# 2014-9-17.net
KiCad netlist of a schematic drawn in Altium Designer
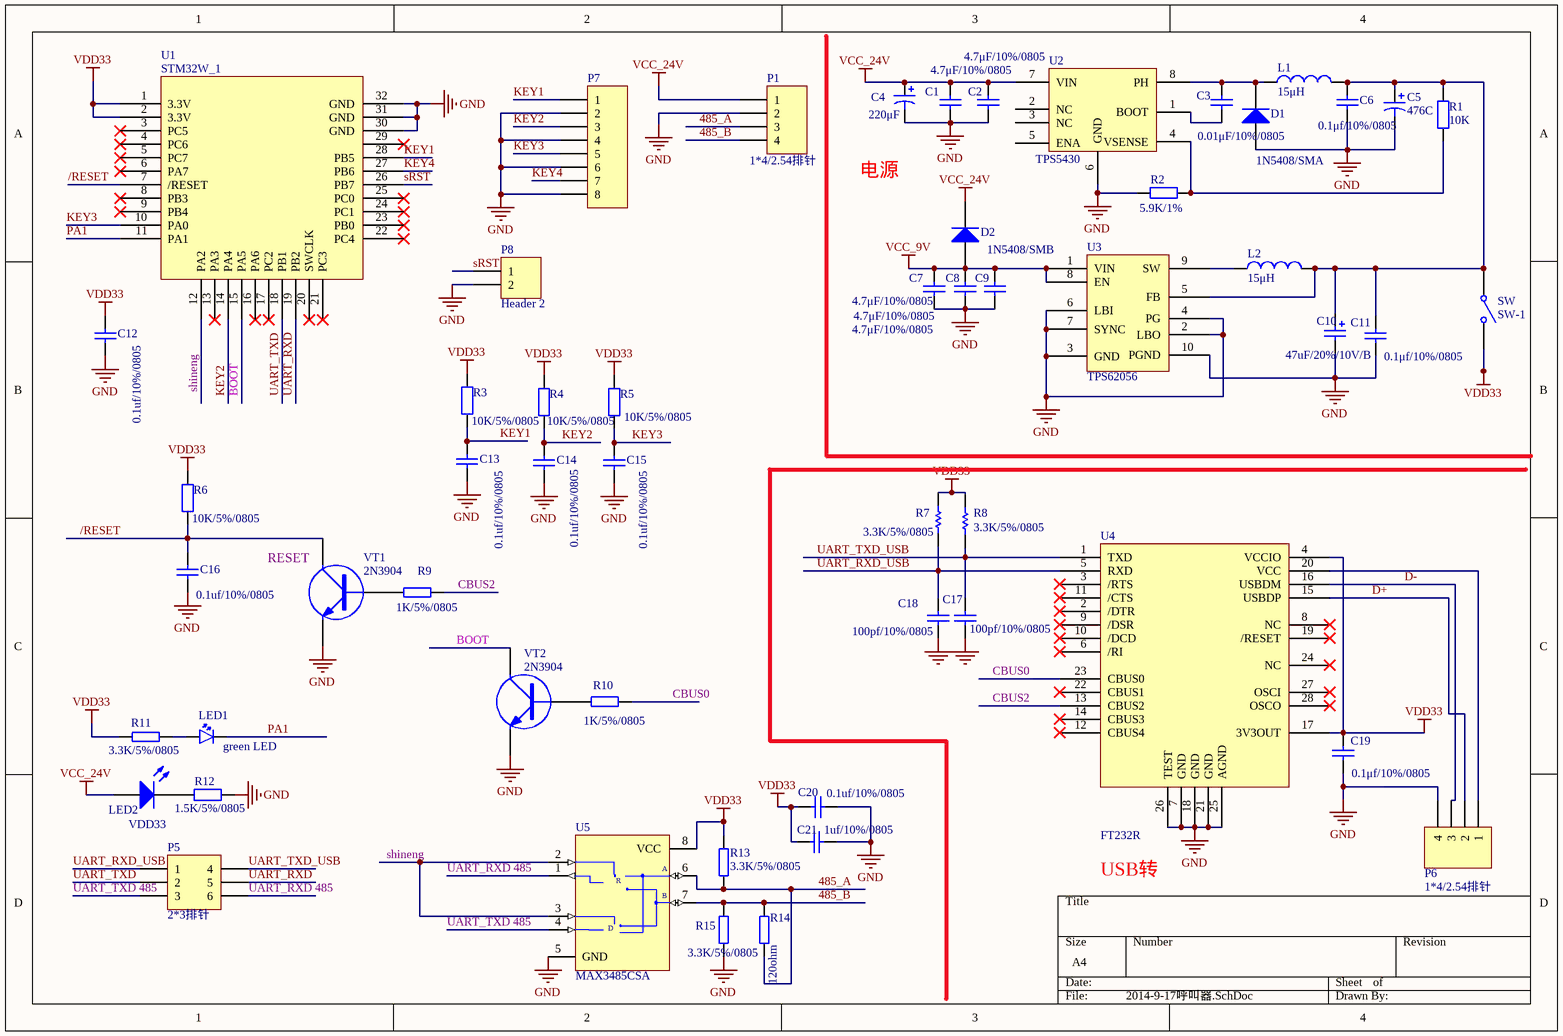
[diagram p0: 2014-9-17呼叫器.SchDoc]

(export (version "E")
  (design (tool "Eeschema 10.0.6"))
  (components
    (comp (ref "C1")
      (value "4.7μF/10%/0805")
      (footprint "C-0805")
      (description "Capacitor")
      (fields (field (name "PUBLISHER") "Altium Limited"))
      (libsource (lib "Miscellaneous Devices") (part "Cap"))
    )
    (comp (ref "C2")
      (value "4.7μF/10%/0805")
      (footprint "C-0805")
      (description "Capacitor")
      (fields (field (name "PUBLISHER") "Altium Limited"))
      (libsource (lib "Miscellaneous Devices") (part "Cap"))
    )
    (comp (ref "C3")
      (value "0.01μF/10%/0805")
      (footprint "C-0805")
      (description "Capacitor")
      (fields (field (name "PUBLISHER") "Altium Limited"))
      (libsource (lib "Miscellaneous Devices") (part "Cap"))
    )
    (comp (ref "C4")
      (value "220μF")
      (footprint "CZ3.0/6.5")
      (description "Polarized Capacitor (Radial)")
      (fields (field (name "PUBLISHER") "Altium Limited"))
      (libsource (lib "Miscellaneous Devices") (part "Cap Pol1"))
    )
    (comp (ref "C5")
      (value "476C")
      (footprint "C-TAN-D")
      (description "Polarized Capacitor (Radial)")
      (fields (field (name "PUBLISHER") "Altium Limited"))
      (libsource (lib "Miscellaneous Devices") (part "Cap Pol1"))
    )
    (comp (ref "C6")
      (value "0.1μf/10%/0805")
      (footprint "C-0805")
      (description "Capacitor")
      (fields (field (name "PUBLISHER") "Altium Limited"))
      (libsource (lib "Miscellaneous Devices") (part "Cap"))
    )
    (comp (ref "C7")
      (value "4.7μF/10%/0805")
      (footprint "C-0805")
      (description "Capacitor")
      (fields (field (name "PUBLISHER") "Altium Limited"))
      (libsource (lib "Miscellaneous Devices") (part "Cap"))
    )
    (comp (ref "C8")
      (value "4.7μF/10%/0805")
      (footprint "C-0805")
      (description "Capacitor")
      (fields (field (name "PUBLISHER") "Altium Limited"))
      (libsource (lib "Miscellaneous Devices") (part "Cap"))
    )
    (comp (ref "C9")
      (value "4.7μF/10%/0805")
      (footprint "C-0805")
      (description "Capacitor")
      (fields (field (name "PUBLISHER") "Altium Limited"))
      (libsource (lib "Miscellaneous Devices") (part "Cap"))
    )
    (comp (ref "C10")
      (value "47uF/20%/10V/B")
      (footprint "C-TAN-B")
      (libsource (lib "浙江关西电机数据库") (part "CAP_polarity"))
    )
    (comp (ref "C11")
      (value "0.1μf/10%/0805")
      (footprint "C-0805")
      (description "Capacitor")
      (fields (field (name "PUBLISHER") "Altium Limited"))
      (libsource (lib "Miscellaneous Devices") (part "Cap"))
    )
    (comp (ref "C12")
      (value "0.1uf/10%/0805")
      (footprint "C-0805")
      (description "Capacitor")
      (fields (field (name "PUBLISHER") "Altium Limited"))
      (libsource (lib "Miscellaneous Devices") (part "Cap"))
    )
    (comp (ref "C13")
      (value "0.1uf/10%/0805")
      (footprint "C-0805")
      (description "Capacitor")
      (fields (field (name "PUBLISHER") "Altium Limited"))
      (libsource (lib "Miscellaneous Devices") (part "Cap"))
    )
    (comp (ref "C14")
      (value "0.1uf/10%/0805")
      (footprint "C-0805")
      (description "Capacitor")
      (fields (field (name "PUBLISHER") "Altium Limited"))
      (libsource (lib "Miscellaneous Devices") (part "Cap"))
    )
    (comp (ref "C15")
      (value "0.1uf/10%/0805")
      (footprint "C-0805")
      (description "Capacitor")
      (fields (field (name "PUBLISHER") "Altium Limited"))
      (libsource (lib "Miscellaneous Devices") (part "Cap"))
    )
    (comp (ref "C16")
      (value "0.1uf/10%/0805")
      (footprint "C-0805")
      (description "Capacitor")
      (fields (field (name "PUBLISHER") "Altium Limited"))
      (libsource (lib "Miscellaneous Devices") (part "Cap"))
    )
    (comp (ref "C17")
      (value "100pf/10%/0805")
      (footprint "C-0805")
      (description "Capacitor")
      (fields (field (name "PUBLISHER") "Altium Limited"))
      (libsource (lib "Miscellaneous Devices") (part "Cap"))
    )
    (comp (ref "C18")
      (value "100pf/10%/0805")
      (footprint "C-0805")
      (description "Capacitor")
      (fields (field (name "PUBLISHER") "Altium Limited"))
      (libsource (lib "Miscellaneous Devices") (part "Cap"))
    )
    (comp (ref "C19")
      (value "0.1μf/10%/0805")
      (footprint "C-0805")
      (description "Capacitor")
      (fields (field (name "PUBLISHER") "Altium Limited"))
      (libsource (lib "Miscellaneous Devices") (part "Cap"))
    )
    (comp (ref "C20")
      (value "0.1uf/10%/0805")
      (footprint "C-0805")
      (description "Capacitor")
      (fields (field (name "PUBLISHER") "Altium Limited"))
      (libsource (lib "Miscellaneous Devices") (part "Cap"))
    )
    (comp (ref "C21")
      (value "1uf/10%/0805")
      (footprint "C-0805")
      (description "Capacitor")
      (fields (field (name "PUBLISHER") "Altium Limited"))
      (libsource (lib "Miscellaneous Devices") (part "Cap"))
    )
    (comp (ref "D1")
      (value "1N5408/SMA")
      (footprint "SMA 2+")
      (description "3 Amp Medium Power Silicon Rectifier Diode")
      (fields (field (name "PUBLISHER") "Altium Limited"))
      (libsource (lib "Miscellaneous Devices") (part "Diode 1N5408"))
    )
    (comp (ref "D2")
      (value "1N5408/SMB")
      (footprint "smb")
      (description "3 Amp Medium Power Silicon Rectifier Diode")
      (fields (field (name "PUBLISHER") "Altium Limited"))
      (libsource (lib "Miscellaneous Devices") (part "Diode 1N5408"))
    )
    (comp (ref "L1")
      (value "15μH")
      (footprint "GSDS104C2")
      (description "Inductor")
      (fields (field (name "PUBLISHER") "Altium Limited"))
      (libsource (lib "Miscellaneous Devices") (part "Inductor"))
    )
    (comp (ref "L2")
      (value "15μH")
      (footprint "GSDS104C2")
      (description "Inductor")
      (fields (field (name "PUBLISHER") "Altium Limited"))
      (libsource (lib "Miscellaneous Devices") (part "Inductor"))
    )
    (comp (ref "LED1") (value "green LED") (footprint "LED-φ3") (libsource (lib "Haze") (part "LED")))
    (comp (ref "LED2")
      (value "VDD33")
      (footprint "LED-φ3")
      (description "Typical BLUE SiC LED")
      (fields (field (name "PUBLISHER") "Altium Limited"))
      (libsource (lib "Miscellaneous Devices") (part "LED3"))
    )
    (comp (ref "P1")
      (value "1*4/2.54排针")
      (footprint "PIN-S-2.54-1*4")
      (description "Header, 4-Pin")
      (fields (field (name "PUBLISHER") "Altium Limited"))
      (libsource (lib "") (part "Header 4_1"))
    )
    (comp (ref "P5")
      (value "2*3排针")
      (footprint "HDR2X3_CEN")
      (description "Header, 3-Pin, Dual row")
      (fields (field (name "PUBLISHER") "Altium Limited"))
      (libsource (lib "Miscellaneous Connectors") (part "Header 3X2A"))
    )
    (comp (ref "P6")
      (value "1*4/2.54排针")
      (footprint "PIN-S-2.54-1*4")
      (description "Header, 4-Pin")
      (fields (field (name "PUBLISHER") "Altium Limited"))
      (libsource (lib "Miscellaneous Connectors") (part "Header 4"))
    )
    (comp (ref "P7")
      (value "Header 8")
      (footprint "HDR1X8")
      (description "Header, 8-Pin")
      (fields (field (name "PUBLISHER") "Altium Limited"))
      (libsource (lib "Miscellaneous Connectors") (part "Header 8"))
    )
    (comp (ref "P8")
      (value "Header 2")
      (footprint "HDR1X2")
      (description "Header, 2-Pin")
      (fields (field (name "PUBLISHER") "Altium Limited"))
      (libsource (lib "Miscellaneous Connectors") (part "Header 2"))
    )
    (comp (ref "R1")
      (value "10K")
      (footprint "R-0805")
      (description "Resistor")
      (fields (field (name "PUBLISHER") "Altium Limited"))
      (libsource (lib "") (part "Res2_1"))
    )
    (comp (ref "R2")
      (value "5.9K/1%")
      (footprint "R-0805")
      (description "Resistor")
      (fields (field (name "PUBLISHER") "Altium Limited"))
      (libsource (lib "Miscellaneous Devices") (part "Res2"))
    )
    (comp (ref "R3")
      (value "10K/5%/0805")
      (footprint "R-0805")
      (description "Resistor")
      (fields (field (name "PUBLISHER") "Altium Limited"))
      (libsource (lib "") (part "Res2_1"))
    )
    (comp (ref "R4")
      (value "10K/5%/0805")
      (footprint "R-0805")
      (description "Resistor")
      (fields (field (name "PUBLISHER") "Altium Limited"))
      (libsource (lib "") (part "Res2_1"))
    )
    (comp (ref "R5")
      (value "10K/5%/0805")
      (footprint "R-0805")
      (description "Resistor")
      (fields (field (name "PUBLISHER") "Altium Limited"))
      (libsource (lib "") (part "Res2_1"))
    )
    (comp (ref "R6")
      (value "10K/5%/0805")
      (footprint "R-0805")
      (description "Resistor")
      (fields (field (name "PUBLISHER") "Altium Limited"))
      (libsource (lib "") (part "Res2_1"))
    )
    (comp (ref "R7")
      (value "3.3K/5%/0805")
      (footprint "R-0805")
      (libsource (lib "SCHLIBRARIES") (part "RES_1"))
    )
    (comp (ref "R8")
      (value "3.3K/5%/0805")
      (footprint "R-0805")
      (libsource (lib "SCHLIBRARIES") (part "RES_1"))
    )
    (comp (ref "R9")
      (value "1K/5%/0805")
      (footprint "R-0805")
      (description "R")
      (libsource (lib "Haze") (part "RES"))
    )
    (comp (ref "R10")
      (value "1K/5%/0805")
      (footprint "R-0805")
      (description "R")
      (libsource (lib "Haze") (part "RES"))
    )
    (comp (ref "R11")
      (value "3.3K/5%/0805")
      (footprint "R-0805")
      (description "R")
      (libsource (lib "Haze") (part "RES"))
    )
    (comp (ref "R12")
      (value "1.5K/5%/0805")
      (footprint "R-0805")
      (description "Resistor")
      (fields (field (name "PUBLISHER") "Altium Limited"))
      (libsource (lib "Miscellaneous Devices") (part "Res2"))
    )
    (comp (ref "R13")
      (value "3.3K/5%/0805")
      (footprint "R-0805")
      (description "R")
      (libsource (lib "Haze") (part "RES"))
    )
    (comp (ref "R14")
      (value "120ohm")
      (footprint "R-0805")
      (description "R")
      (libsource (lib "Haze") (part "RES"))
    )
    (comp (ref "R15")
      (value "3.3K/5%/0805")
      (footprint "R-0805")
      (description "R")
      (libsource (lib "Haze") (part "RES"))
    )
    (comp (ref "SW")
      (value "SW-1")
      (footprint "PIN-S-2.54-1*2")
      (libsource (lib "SCHLIBRARIES") (part "SW-1"))
    )
    (comp (ref "U1")
      (value "STM32W_1")
      (footprint "STM32W108-3")
      (libsource (lib "STM32W108-3") (part "STM32W108-3"))
    )
    (comp (ref "U2") (value "TPS5430") (footprint "SO-G8") (libsource (lib "SCHLIBRARIES") (part "TPS5430")))
    (comp (ref "U3")
      (value "TPS62056")
      (footprint "MSOP-10")
      (libsource (lib "SCHLIBRARIES") (part "TPS62056"))
    )
    (comp (ref "U4") (value "FT232R") (footprint "SSOP-28") (libsource (lib "Haze") (part "FT232R")))
    (comp (ref "U5")
      (value "MAX3485CSA")
      (footprint "SO-G8")
      (description "Low-Power, Slew-Rate-Limited RS-485/RS-422 Transceiver")
      (fields (field (name "PUBLISHER") "Altium Limited"))
      (libsource (lib "Maxim Communication Transceiver") (part "MAX485CSA"))
    )
    (comp (ref "VT1")
      (value "2N3904")
      (footprint "SOT23-3")
      (description "NPN Transistor")
      (libsource (lib "Haze") (part "NPN"))
    )
    (comp (ref "VT2")
      (value "2N3904")
      (footprint "SOT23-3")
      (description "NPN Transistor")
      (libsource (lib "Haze") (part "NPN"))
    )
  )
  (nets
    (net (code "1") (name "/485_A") (class "Default")
      (node (ref "P1") (pin "3") (pinfunction "3_3") (pintype "passive"))
      (node (ref "R13") (pin "1") (pinfunction "1_1") (pintype "passive"))
      (node (ref "R14") (pin "2") (pinfunction "2_2") (pintype "passive"))
      (node (ref "U5") (pin "6") (pinfunction "A_6") (pintype "bidirectional"))
    )
    (net (code "2") (name "/485_B") (class "Default")
      (node (ref "P1") (pin "4") (pinfunction "4_4") (pintype "passive"))
      (node (ref "R14") (pin "1") (pinfunction "1_1") (pintype "passive"))
      (node (ref "R15") (pin "2") (pinfunction "2_2") (pintype "passive"))
      (node (ref "U5") (pin "7") (pinfunction "B_7") (pintype "bidirectional"))
    )
    (net (code "3") (name "/BOOT") (class "Default")
      (node (ref "U1") (pin "15") (pinfunction "PA5_15") (pintype "passive"))
      (node (ref "VT2") (pin "3") (pinfunction "C_3") (pintype "passive"))
    )
    (net (code "4") (name "/CBUS0") (class "Default")
      (node (ref "R10") (pin "2") (pinfunction "2_2") (pintype "passive"))
      (node (ref "U4") (pin "23") (pinfunction "CBUS0_23") (pintype "passive"))
    )
    (net (code "5") (name "/CBUS2") (class "Default")
      (node (ref "R9") (pin "2") (pinfunction "2_2") (pintype "passive"))
      (node (ref "U4") (pin "13") (pinfunction "CBUS2_13") (pintype "passive"))
    )
    (net (code "6") (name "/D+") (class "Default")
      (node (ref "P6") (pin "2") (pinfunction "2_2") (pintype "passive"))
      (node (ref "U4") (pin "15") (pinfunction "USBDP_15") (pintype "passive"))
    )
    (net (code "7") (name "/D-") (class "Default")
      (node (ref "P6") (pin "3") (pinfunction "3_3") (pintype "passive"))
      (node (ref "U4") (pin "16") (pinfunction "USBDM_16") (pintype "passive"))
    )
    (net (code "8") (name "/KEY1") (class "Default")
      (node (ref "C13") (pin "2") (pinfunction "2_2") (pintype "passive"))
      (node (ref "P7") (pin "1") (pinfunction "1_1") (pintype "passive"))
      (node (ref "R3") (pin "1") (pinfunction "1_1") (pintype "passive"))
      (node (ref "U1") (pin "28") (pinfunction "PB5_28") (pintype "passive"))
    )
    (net (code "9") (name "/KEY2") (class "Default")
      (node (ref "C14") (pin "2") (pinfunction "2_2") (pintype "passive"))
      (node (ref "P7") (pin "3") (pinfunction "3_3") (pintype "passive"))
      (node (ref "R4") (pin "1") (pinfunction "1_1") (pintype "passive"))
      (node (ref "U1") (pin "14") (pinfunction "PA4_14") (pintype "passive"))
    )
    (net (code "10") (name "/KEY3") (class "Default")
      (node (ref "C15") (pin "2") (pinfunction "2_2") (pintype "passive"))
      (node (ref "P7") (pin "5") (pinfunction "5_5") (pintype "passive"))
      (node (ref "R5") (pin "1") (pinfunction "1_1") (pintype "passive"))
      (node (ref "U1") (pin "10") (pinfunction "PA0_10") (pintype "passive"))
    )
    (net (code "11") (name "/KEY4") (class "Default")
      (node (ref "P7") (pin "7") (pinfunction "7_7") (pintype "passive"))
      (node (ref "U1") (pin "27") (pinfunction "PB6_27") (pintype "passive"))
    )
    (net (code "12") (name "/PA1") (class "Default")
      (node (ref "LED1") (pin "2") (pinfunction "K_2") (pintype "passive"))
      (node (ref "U1") (pin "11") (pinfunction "PA1_11") (pintype "passive"))
    )
    (net (code "13") (name "/UART_RXD") (class "Default")
      (node (ref "P5") (pin "5") (pinfunction "5_5") (pintype "passive"))
      (node (ref "U1") (pin "19") (pinfunction "PB2_19") (pintype "passive"))
    )
    (net (code "14") (name "/UART_RXD 485") (class "Default")
      (node (ref "P5") (pin "6") (pinfunction "6_6") (pintype "passive"))
      (node (ref "U5") (pin "1") (pinfunction "RO_1") (pintype "output"))
    )
    (net (code "15") (name "/UART_RXD_USB") (class "Default")
      (node (ref "C18") (pin "2") (pinfunction "2_2") (pintype "passive"))
      (node (ref "P5") (pin "1") (pinfunction "1_1") (pintype "passive"))
      (node (ref "R7") (pin "1") (pinfunction "1_1") (pintype "passive"))
      (node (ref "U4") (pin "5") (pinfunction "RXD_5") (pintype "passive"))
    )
    (net (code "16") (name "/UART_TXD") (class "Default")
      (node (ref "P5") (pin "2") (pinfunction "2_2") (pintype "passive"))
      (node (ref "U1") (pin "18") (pinfunction "PB1_18") (pintype "passive"))
    )
    (net (code "17") (name "/UART_TXD 485") (class "Default")
      (node (ref "P5") (pin "3") (pinfunction "3_3") (pintype "passive"))
      (node (ref "U5") (pin "4") (pinfunction "DI_4") (pintype "input"))
    )
    (net (code "18") (name "/UART_TXD_USB") (class "Default")
      (node (ref "C17") (pin "2") (pinfunction "2_2") (pintype "passive"))
      (node (ref "P5") (pin "4") (pinfunction "4_4") (pintype "passive"))
      (node (ref "R8") (pin "1") (pinfunction "1_1") (pintype "passive"))
      (node (ref "U4") (pin "1") (pinfunction "TXD_1") (pintype "passive"))
    )
    (net (code "19") (name "/sRST") (class "Default")
      (node (ref "P8") (pin "1") (pinfunction "1_1") (pintype "passive"))
      (node (ref "U1") (pin "26") (pinfunction "PB7_26") (pintype "passive"))
    )
    (net (code "20") (name "/shineng") (class "Default")
      (node (ref "U1") (pin "12") (pinfunction "PA2_12") (pintype "passive"))
      (node (ref "U5") (pin "2") (pinfunction "~{RE}_2") (pintype "input"))
      (node (ref "U5") (pin "3") (pinfunction "DE_3") (pintype "input"))
    )
    (net (code "21") (name "/{slash}RESET") (class "Default")
      (node (ref "C16") (pin "2") (pinfunction "2_2") (pintype "passive"))
      (node (ref "R6") (pin "1") (pinfunction "1_1") (pintype "passive"))
      (node (ref "U1") (pin "7") (pinfunction "/RESET_7") (pintype "passive"))
      (node (ref "VT1") (pin "3") (pinfunction "C_3") (pintype "passive"))
    )
    (net (code "22") (name "GND") (class "Default")
      (node (ref "C1") (pin "1") (pinfunction "1_1") (pintype "passive"))
      (node (ref "C10") (pin "2") (pinfunction "2_2") (pintype "passive"))
      (node (ref "C11") (pin "1") (pinfunction "1_1") (pintype "passive"))
      (node (ref "C12") (pin "1") (pinfunction "1_1") (pintype "passive"))
      (node (ref "C13") (pin "1") (pinfunction "1_1") (pintype "passive"))
      (node (ref "C14") (pin "1") (pinfunction "1_1") (pintype "passive"))
      (node (ref "C15") (pin "1") (pinfunction "1_1") (pintype "passive"))
      (node (ref "C16") (pin "1") (pinfunction "1_1") (pintype "passive"))
      (node (ref "C17") (pin "1") (pinfunction "1_1") (pintype "passive"))
      (node (ref "C18") (pin "1") (pinfunction "1_1") (pintype "passive"))
      (node (ref "C19") (pin "1") (pinfunction "1_1") (pintype "passive"))
      (node (ref "C2") (pin "1") (pinfunction "1_1") (pintype "passive"))
      (node (ref "C20") (pin "1") (pinfunction "1_1") (pintype "passive"))
      (node (ref "C21") (pin "1") (pinfunction "1_1") (pintype "passive"))
      (node (ref "C4") (pin "2") (pinfunction "2_2") (pintype "passive"))
      (node (ref "C5") (pin "2") (pinfunction "2_2") (pintype "passive"))
      (node (ref "C6") (pin "1") (pinfunction "1_1") (pintype "passive"))
      (node (ref "C7") (pin "1") (pinfunction "1_1") (pintype "passive"))
      (node (ref "C8") (pin "1") (pinfunction "1_1") (pintype "passive"))
      (node (ref "C9") (pin "1") (pinfunction "1_1") (pintype "passive"))
      (node (ref "D1") (pin "1") (pinfunction "A_1") (pintype "passive"))
      (node (ref "P1") (pin "2") (pinfunction "2_2") (pintype "passive"))
      (node (ref "P6") (pin "4") (pinfunction "4_4") (pintype "passive"))
      (node (ref "P7") (pin "2") (pinfunction "2_2") (pintype "passive"))
      (node (ref "P7") (pin "4") (pinfunction "4_4") (pintype "passive"))
      (node (ref "P7") (pin "6") (pinfunction "6_6") (pintype "passive"))
      (node (ref "P7") (pin "8") (pinfunction "8_8") (pintype "passive"))
      (node (ref "P8") (pin "2") (pinfunction "2_2") (pintype "passive"))
      (node (ref "R12") (pin "1") (pinfunction "1_1") (pintype "passive"))
      (node (ref "R15") (pin "1") (pinfunction "1_1") (pintype "passive"))
      (node (ref "R2") (pin "2") (pinfunction "2_2") (pintype "passive"))
      (node (ref "U1") (pin "30") (pinfunction "GND_30") (pintype "passive"))
      (node (ref "U1") (pin "31") (pinfunction "GND_31") (pintype "passive"))
      (node (ref "U1") (pin "32") (pinfunction "GND_32") (pintype "passive"))
      (node (ref "U2") (pin "6") (pinfunction "GND_6") (pintype "passive"))
      (node (ref "U3") (pin "10") (pinfunction "PGND_10") (pintype "passive"))
      (node (ref "U3") (pin "2") (pinfunction "LBO_2") (pintype "passive"))
      (node (ref "U3") (pin "3") (pinfunction "GND_3") (pintype "passive"))
      (node (ref "U3") (pin "4") (pinfunction "PG_4") (pintype "passive"))
      (node (ref "U3") (pin "6") (pinfunction "LBI_6") (pintype "passive"))
      (node (ref "U3") (pin "7") (pinfunction "SYNC_7") (pintype "passive"))
      (node (ref "U4") (pin "18") (pinfunction "GND_18") (pintype "passive"))
      (node (ref "U4") (pin "21") (pinfunction "GND_21") (pintype "passive"))
      (node (ref "U4") (pin "25") (pinfunction "AGND_25") (pintype "passive"))
      (node (ref "U4") (pin "26") (pinfunction "TEST_26") (pintype "passive"))
      (node (ref "U4") (pin "7") (pinfunction "GND_7") (pintype "passive"))
      (node (ref "U5") (pin "5") (pinfunction "GND_5") (pintype "power_in"))
      (node (ref "VT1") (pin "2") (pinfunction "E_2") (pintype "passive"))
      (node (ref "VT2") (pin "2") (pinfunction "E_2") (pintype "passive"))
    )
    (net (code "23") (name "Net-(D1-K)") (class "Default")
      (node (ref "C3") (pin "2") (pinfunction "2_2") (pintype "passive"))
      (node (ref "D1") (pin "2") (pinfunction "K_2") (pintype "passive"))
      (node (ref "L1") (pin "1") (pinfunction "1_1") (pintype "passive"))
      (node (ref "U2") (pin "8") (pinfunction "PH_8") (pintype "passive"))
    )
    (net (code "24") (name "Net-(LED1-A)") (class "Default")
      (node (ref "LED1") (pin "1") (pinfunction "A_1") (pintype "passive"))
      (node (ref "R11") (pin "2") (pinfunction "2_2") (pintype "passive"))
    )
    (net (code "25") (name "Net-(LED2-K)") (class "Default")
      (node (ref "LED2") (pin "2") (pinfunction "K_2") (pintype "passive"))
      (node (ref "R12") (pin "2") (pinfunction "2_2") (pintype "passive"))
    )
    (net (code "26") (name "Net-(U2-BOOT)") (class "Default")
      (node (ref "C3") (pin "1") (pinfunction "1_1") (pintype "passive"))
      (node (ref "U2") (pin "1") (pinfunction "BOOT_1") (pintype "passive"))
    )
    (net (code "27") (name "Net-(U2-VSENSE)") (class "Default")
      (node (ref "R1") (pin "1") (pinfunction "1_1") (pintype "passive"))
      (node (ref "R2") (pin "1") (pinfunction "1_1") (pintype "passive"))
      (node (ref "U2") (pin "4") (pinfunction "VSENSE_4") (pintype "passive"))
    )
    (net (code "28") (name "Net-(U3-FB)") (class "Default")
      (node (ref "C10") (pin "1") (pinfunction "1_1") (pintype "passive"))
      (node (ref "C11") (pin "2") (pinfunction "2_2") (pintype "passive"))
      (node (ref "C5") (pin "1") (pinfunction "1_1") (pintype "passive"))
      (node (ref "C6") (pin "2") (pinfunction "2_2") (pintype "passive"))
      (node (ref "L1") (pin "2") (pinfunction "2_2") (pintype "passive"))
      (node (ref "L2") (pin "2") (pinfunction "2_2") (pintype "passive"))
      (node (ref "R1") (pin "2") (pinfunction "2_2") (pintype "passive"))
      (node (ref "SW") (pin "1") (pinfunction "1_1") (pintype "passive"))
      (node (ref "U3") (pin "5") (pinfunction "FB_5") (pintype "passive"))
    )
    (net (code "29") (name "Net-(U3-SW)") (class "Default")
      (node (ref "L2") (pin "1") (pinfunction "1_1") (pintype "passive"))
      (node (ref "U3") (pin "9") (pinfunction "SW_9") (pintype "passive"))
    )
    (net (code "30") (name "Net-(U4-VCC)") (class "Default")
      (node (ref "P6") (pin "1") (pinfunction "1_1") (pintype "passive"))
      (node (ref "U4") (pin "20") (pinfunction "VCC_20") (pintype "passive"))
    )
    (net (code "31") (name "Net-(VT1-B)") (class "Default")
      (node (ref "R9") (pin "1") (pinfunction "1_1") (pintype "passive"))
      (node (ref "VT1") (pin "1") (pinfunction "B_1") (pintype "passive"))
    )
    (net (code "32") (name "Net-(VT2-B)") (class "Default")
      (node (ref "R10") (pin "1") (pinfunction "1_1") (pintype "passive"))
      (node (ref "VT2") (pin "1") (pinfunction "B_1") (pintype "passive"))
    )
    (net (code "33") (name "VCC_9V") (class "Default")
      (node (ref "C7") (pin "2") (pinfunction "2_2") (pintype "passive"))
      (node (ref "C8") (pin "2") (pinfunction "2_2") (pintype "passive"))
      (node (ref "C9") (pin "2") (pinfunction "2_2") (pintype "passive"))
      (node (ref "D2") (pin "1") (pinfunction "A_1") (pintype "passive"))
      (node (ref "U3") (pin "1") (pinfunction "VIN_1") (pintype "passive"))
      (node (ref "U3") (pin "8") (pinfunction "EN_8") (pintype "passive"))
    )
    (net (code "34") (name "VCC_24V") (class "Default")
      (node (ref "C1") (pin "2") (pinfunction "2_2") (pintype "passive"))
      (node (ref "C2") (pin "2") (pinfunction "2_2") (pintype "passive"))
      (node (ref "C4") (pin "1") (pinfunction "1_1") (pintype "passive"))
      (node (ref "D2") (pin "2") (pinfunction "K_2") (pintype "passive"))
      (node (ref "LED2") (pin "1") (pinfunction "A_1") (pintype "passive"))
      (node (ref "P1") (pin "1") (pinfunction "1_1") (pintype "passive"))
      (node (ref "U2") (pin "7") (pinfunction "VIN_7") (pintype "passive"))
    )
    (net (code "35") (name "VDD33") (class "Default")
      (node (ref "C12") (pin "2") (pinfunction "2_2") (pintype "passive"))
      (node (ref "C19") (pin "2") (pinfunction "2_2") (pintype "passive"))
      (node (ref "C20") (pin "2") (pinfunction "2_2") (pintype "passive"))
      (node (ref "C21") (pin "2") (pinfunction "2_2") (pintype "passive"))
      (node (ref "R11") (pin "1") (pinfunction "1_1") (pintype "passive"))
      (node (ref "R13") (pin "2") (pinfunction "2_2") (pintype "passive"))
      (node (ref "R3") (pin "2") (pinfunction "2_2") (pintype "passive"))
      (node (ref "R4") (pin "2") (pinfunction "2_2") (pintype "passive"))
      (node (ref "R5") (pin "2") (pinfunction "2_2") (pintype "passive"))
      (node (ref "R6") (pin "2") (pinfunction "2_2") (pintype "passive"))
      (node (ref "R7") (pin "2") (pinfunction "2_2") (pintype "passive"))
      (node (ref "R8") (pin "2") (pinfunction "2_2") (pintype "passive"))
      (node (ref "SW") (pin "2") (pinfunction "2_2") (pintype "passive"))
      (node (ref "U1") (pin "1") (pinfunction "3.3V_1") (pintype "passive"))
      (node (ref "U1") (pin "2") (pinfunction "3.3V_2") (pintype "passive"))
      (node (ref "U4") (pin "17") (pinfunction "3V3OUT_17") (pintype "passive"))
      (node (ref "U4") (pin "4") (pinfunction "VCCIO_4") (pintype "passive"))
      (node (ref "U5") (pin "8") (pinfunction "VCC_8") (pintype "power_in"))
    )
    (net (code "36") (name "unconnected-(U1-PA3-Pad13)") (class "Default")
      (node (ref "U1") (pin "13") (pinfunction "PA3_13") (pintype "passive+no_connect"))
    )
    (net (code "37") (name "unconnected-(U1-PA6-Pad16)") (class "Default")
      (node (ref "U1") (pin "16") (pinfunction "PA6_16") (pintype "passive+no_connect"))
    )
    (net (code "38") (name "unconnected-(U1-PA7-Pad6)") (class "Default")
      (node (ref "U1") (pin "6") (pinfunction "PA7_6") (pintype "passive+no_connect"))
    )
    (net (code "39") (name "unconnected-(U1-PB0-Pad23)") (class "Default")
      (node (ref "U1") (pin "23") (pinfunction "PB0_23") (pintype "passive+no_connect"))
    )
    (net (code "40") (name "unconnected-(U1-PB3-Pad8)") (class "Default")
      (node (ref "U1") (pin "8") (pinfunction "PB3_8") (pintype "passive+no_connect"))
    )
    (net (code "41") (name "unconnected-(U1-PB4-Pad9)") (class "Default")
      (node (ref "U1") (pin "9") (pinfunction "PB4_9") (pintype "passive+no_connect"))
    )
    (net (code "42") (name "unconnected-(U1-PC0-Pad25)") (class "Default")
      (node (ref "U1") (pin "25") (pinfunction "PC0_25") (pintype "passive+no_connect"))
    )
    (net (code "43") (name "unconnected-(U1-PC1-Pad24)") (class "Default")
      (node (ref "U1") (pin "24") (pinfunction "PC1_24") (pintype "passive+no_connect"))
    )
    (net (code "44") (name "unconnected-(U1-PC2-Pad17)") (class "Default")
      (node (ref "U1") (pin "17") (pinfunction "PC2_17") (pintype "passive+no_connect"))
    )
    (net (code "45") (name "unconnected-(U1-PC3-Pad21)") (class "Default")
      (node (ref "U1") (pin "21") (pinfunction "PC3_21") (pintype "passive+no_connect"))
    )
    (net (code "46") (name "unconnected-(U1-PC4-Pad22)") (class "Default")
      (node (ref "U1") (pin "22") (pinfunction "PC4_22") (pintype "passive+no_connect"))
    )
    (net (code "47") (name "unconnected-(U1-PC5-Pad3)") (class "Default")
      (node (ref "U1") (pin "3") (pinfunction "PC5_3") (pintype "passive+no_connect"))
    )
    (net (code "48") (name "unconnected-(U1-PC6-Pad4)") (class "Default")
      (node (ref "U1") (pin "4") (pinfunction "PC6_4") (pintype "passive+no_connect"))
    )
    (net (code "49") (name "unconnected-(U1-PC7-Pad5)") (class "Default")
      (node (ref "U1") (pin "5") (pinfunction "PC7_5") (pintype "passive+no_connect"))
    )
    (net (code "50") (name "unconnected-(U1-Pad29)") (class "Default")
      (node (ref "U1") (pin "29") (pintype "passive+no_connect"))
    )
    (net (code "51") (name "unconnected-(U1-SWCLK-Pad20)") (class "Default")
      (node (ref "U1") (pin "20") (pinfunction "SWCLK_20") (pintype "passive+no_connect"))
    )
    (net (code "52") (name "unconnected-(U2-ENA-Pad5)") (class "Default")
      (node (ref "U2") (pin "5") (pinfunction "ENA_5") (pintype "passive"))
    )
    (net (code "53") (name "unconnected-(U2-NC-Pad2)") (class "Default")
      (node (ref "U2") (pin "2") (pinfunction "NC_2") (pintype "passive"))
    )
    (net (code "54") (name "unconnected-(U2-NC-Pad3)") (class "Default")
      (node (ref "U2") (pin "3") (pinfunction "NC_3") (pintype "passive"))
    )
    (net (code "55") (name "unconnected-(U4-CBUS1-Pad22)") (class "Default")
      (node (ref "U4") (pin "22") (pinfunction "CBUS1_22") (pintype "passive+no_connect"))
    )
    (net (code "56") (name "unconnected-(U4-CBUS3-Pad14)") (class "Default")
      (node (ref "U4") (pin "14") (pinfunction "CBUS3_14") (pintype "passive+no_connect"))
    )
    (net (code "57") (name "unconnected-(U4-CBUS4-Pad12)") (class "Default")
      (node (ref "U4") (pin "12") (pinfunction "CBUS4_12") (pintype "passive+no_connect"))
    )
    (net (code "58") (name "unconnected-(U4-NC-Pad8)") (class "Default")
      (node (ref "U4") (pin "8") (pinfunction "NC_8") (pintype "passive+no_connect"))
    )
    (net (code "59") (name "unconnected-(U4-NC-Pad24)") (class "Default")
      (node (ref "U4") (pin "24") (pinfunction "NC_24") (pintype "passive+no_connect"))
    )
    (net (code "60") (name "unconnected-(U4-OSCI-Pad27)") (class "Default")
      (node (ref "U4") (pin "27") (pinfunction "OSCI_27") (pintype "passive+no_connect"))
    )
    (net (code "61") (name "unconnected-(U4-OSCO-Pad28)") (class "Default")
      (node (ref "U4") (pin "28") (pinfunction "OSCO_28") (pintype "passive+no_connect"))
    )
    (net (code "62") (name "unconnected-(U4-{slash}CTS-Pad11)") (class "Default")
      (node (ref "U4") (pin "11") (pinfunction "/CTS_11") (pintype "passive+no_connect"))
    )
    (net (code "63") (name "unconnected-(U4-{slash}DCD-Pad10)") (class "Default")
      (node (ref "U4") (pin "10") (pinfunction "/DCD_10") (pintype "passive+no_connect"))
    )
    (net (code "64") (name "unconnected-(U4-{slash}DSR-Pad9)") (class "Default")
      (node (ref "U4") (pin "9") (pinfunction "/DSR_9") (pintype "passive+no_connect"))
    )
    (net (code "65") (name "unconnected-(U4-{slash}DTR-Pad2)") (class "Default")
      (node (ref "U4") (pin "2") (pinfunction "/DTR_2") (pintype "passive+no_connect"))
    )
    (net (code "66") (name "unconnected-(U4-{slash}RESET-Pad19)") (class "Default")
      (node (ref "U4") (pin "19") (pinfunction "/RESET_19") (pintype "passive+no_connect"))
    )
    (net (code "67") (name "unconnected-(U4-{slash}RI-Pad6)") (class "Default")
      (node (ref "U4") (pin "6") (pinfunction "/RI_6") (pintype "passive+no_connect"))
    )
    (net (code "68") (name "unconnected-(U4-{slash}RTS-Pad3)") (class "Default")
      (node (ref "U4") (pin "3") (pinfunction "/RTS_3") (pintype "passive+no_connect"))
    )
  )
)
